# CONNECTOR.net
KiCad netlist of a schematic drawn in Altium Designer
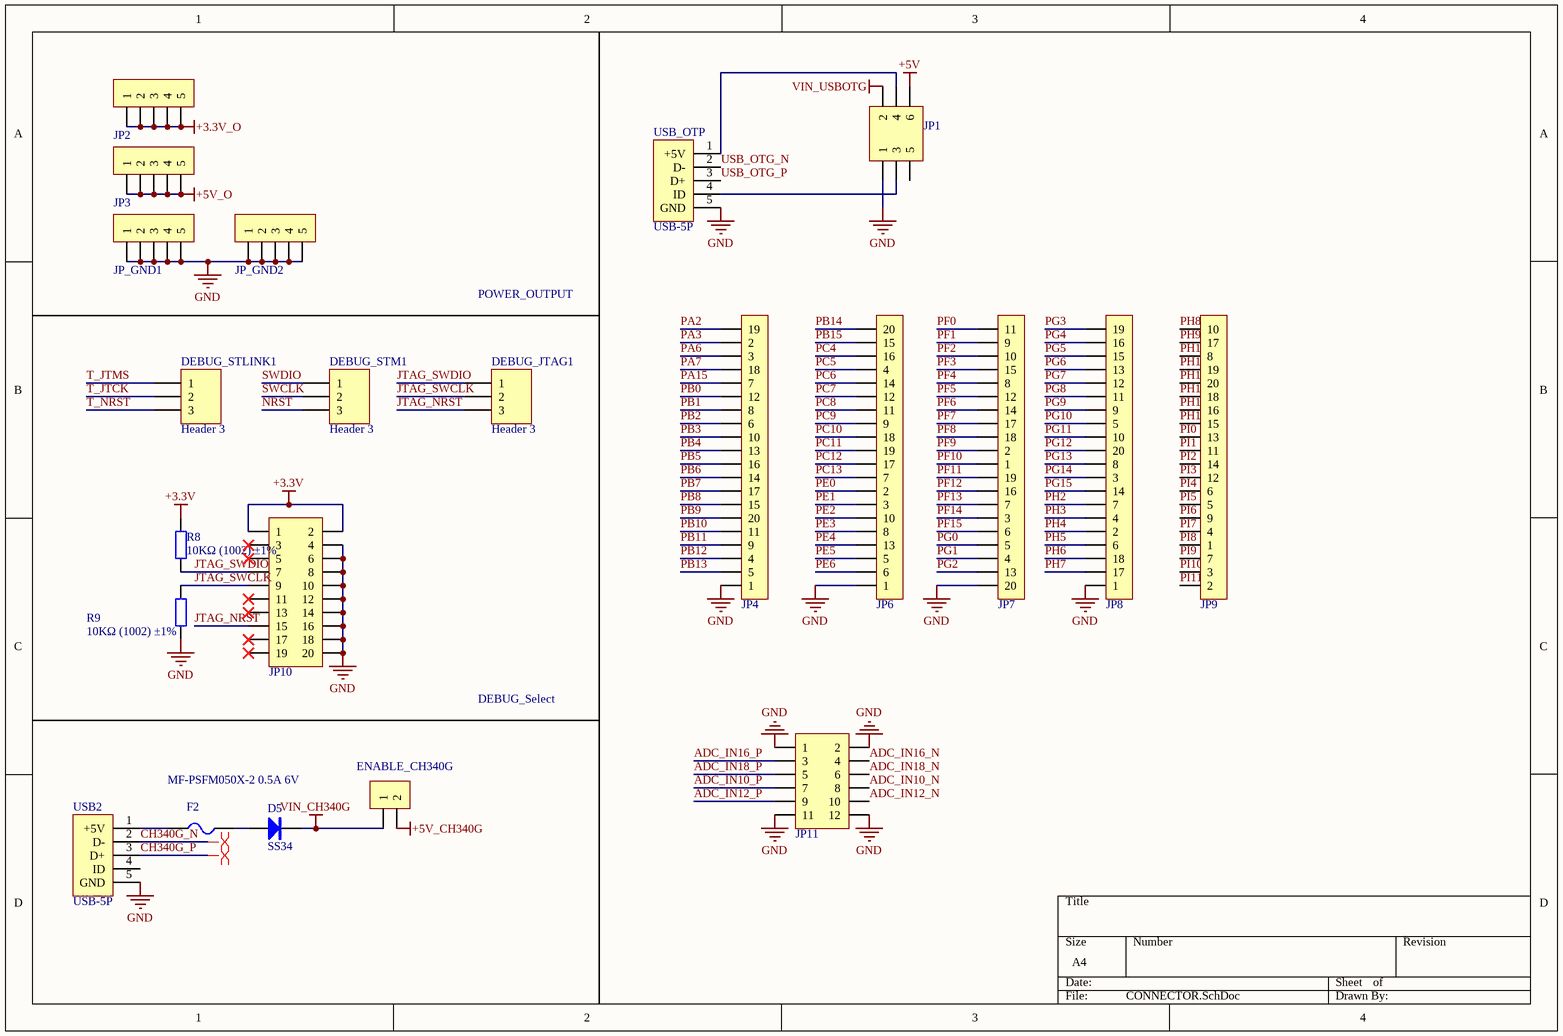
[diagram p0: CONNECTOR.SchDoc]

(export (version "E")
  (design (tool "Eeschema 10.0.6"))
  (components
    (comp (ref "D5")
      (value "SS34")
      (footprint "SMC")
      (description "肖特基二极管")
      (fields (field (name "版权归属") "源创客"))
      (libsource (lib "8.1   - 二极管-整流桥") (part "SS34"))
    )
    (comp (ref "DEBUG_JTAG1")
      (value "Header 3")
      (footprint "HDR1X3")
      (description "Header, 3-Pin")
      (fields (field (name "PUBLISHER") "Altium Limited"))
      (libsource (lib "Miscellaneous Connectors") (part "Header 3"))
    )
    (comp (ref "DEBUG_STLINK1")
      (value "Header 3")
      (footprint "HDR1X3")
      (description "Header, 3-Pin")
      (fields (field (name "PUBLISHER") "Altium Limited"))
      (libsource (lib "Miscellaneous Connectors") (part "Header 3"))
    )
    (comp (ref "DEBUG_STM1")
      (value "Header 3")
      (footprint "HDR1X3")
      (description "Header, 3-Pin")
      (fields (field (name "PUBLISHER") "Altium Limited"))
      (libsource (lib "Miscellaneous Connectors") (part "Header 3"))
    )
    (comp (ref "ENABLE_CH340G")
      (value "HDR-1X2")
      (footprint "HDR2.54-LI-2P")
      (description "2P接插件")
      (fields (field (name "版权归属") "源创客"))
      (libsource (lib "4.5   - 接插件-脚距2.54") (part "Header 2"))
    )
    (comp (ref "F2")
      (value "MF-PSFM050X-2 0.5A 6V")
      (footprint "FU 0805")
      (description "贴片保险丝")
      (fields (field (name "版权归属") "源创客"))
      (libsource (lib "10.1 - 保险丝-晶振") (part "FU"))
    )
    (comp (ref "JP1")
      (value "Header3X2")
      (footprint "HDR2.54-LI-2x3P")
      (description "3*2P接插件")
      (fields (field (name "版权归属") "源创客"))
      (libsource (lib "4.5   - 接插件-脚距2.54") (part "Header 3X2"))
    )
    (comp (ref "JP2")
      (value "HDR-1X5")
      (footprint "HDR2.54-LI-5P")
      (description "5P接插件")
      (fields (field (name "版权归属") "源创客"))
      (libsource (lib "4.5   - 接插件-脚距2.54") (part "Header 5"))
    )
    (comp (ref "JP3")
      (value "HDR-1X5")
      (footprint "HDR2.54-LI-5P")
      (description "5P接插件")
      (fields (field (name "版权归属") "源创客"))
      (libsource (lib "4.5   - 接插件-脚距2.54") (part "Header 5"))
    )
    (comp (ref "JP4")
      (value "HDR-1X20")
      (footprint "HDR2.54-LI-20P")
      (description "20P接插件")
      (fields (field (name "版权归属") "源创客"))
      (libsource (lib "4.5   - 接插件-脚距2.54") (part "Header 20"))
    )
    (comp (ref "JP6")
      (value "HDR-1X20")
      (footprint "HDR2.54-LI-20P")
      (description "20P接插件")
      (fields (field (name "版权归属") "源创客"))
      (libsource (lib "") (part "Header 20_1"))
    )
    (comp (ref "JP7")
      (value "HDR-1X20")
      (footprint "HDR2.54-LI-20P")
      (description "20P接插件")
      (fields (field (name "版权归属") "源创客"))
      (libsource (lib "") (part "Header 20_3"))
    )
    (comp (ref "JP8")
      (value "HDR-1X20")
      (footprint "HDR2.54-LI-20P")
      (description "20P接插件")
      (fields (field (name "版权归属") "源创客"))
      (libsource (lib "") (part "Header 20_2"))
    )
    (comp (ref "JP9")
      (value "HDR-1X20")
      (footprint "HDR2.54-LI-20P")
      (description "20P接插件")
      (fields (field (name "版权归属") "源创客"))
      (libsource (lib "") (part "Header 20_4"))
    )
    (comp (ref "JP10")
      (value "Header 2X10")
      (footprint "IDC2.54-LI-2x10P")
      (description "10*2P接插件")
      (fields (field (name "版权归属") "源创客"))
      (libsource (lib "4.5   - 接插件-脚距2.54") (part "Header 10X2"))
    )
    (comp (ref "JP11")
      (value "Header 6X2")
      (footprint "HDR2.54-LI-2x6P")
      (description "6*2P接插件")
      (fields (field (name "版权归属") "源创客"))
      (libsource (lib "4.5   - 接插件-脚距2.54") (part "Header  6X2"))
    )
    (comp (ref "JP_GND1")
      (value "HDR-1X5")
      (footprint "HDR2.54-LI-5P")
      (description "5P接插件")
      (fields (field (name "版权归属") "源创客"))
      (libsource (lib "4.5   - 接插件-脚距2.54") (part "Header 5"))
    )
    (comp (ref "JP_GND2")
      (value "HDR-1X5")
      (footprint "HDR2.54-LI-5P")
      (description "5P接插件")
      (fields (field (name "版权归属") "源创客"))
      (libsource (lib "4.5   - 接插件-脚距2.54") (part "Header 5"))
    )
    (comp (ref "R8")
      (value "10KΩ (1002) ±1%")
      (footprint "0603_R")
      (description "贴片电阻")
      (libsource (lib "RES") (part "0603 10KΩ (1002) 1%"))
    )
    (comp (ref "R9")
      (value "10KΩ (1002) ±1%")
      (footprint "0603_R")
      (description "贴片电阻")
      (libsource (lib "RES") (part "0603 10KΩ (1002) 1%"))
    )
    (comp (ref "USB2")
      (value "USB-5P")
      (footprint "USB-MICRO_D")
      (description "微型USB母座")
      (fields (field (name "版权归属") "源创客"))
      (libsource (lib "4.1   - 接口类") (part "USB-5P"))
    )
    (comp (ref "USB_OTP")
      (value "USB-5P")
      (footprint "USB-MICRO_D")
      (description "微型USB母座")
      (fields (field (name "版权归属") "源创客"))
      (libsource (lib "4.1   - 接口类") (part "USB-5P"))
    )
  )
  (nets
    (net (code "1") (name "+3.3V") (class "Default")
      (node (ref "JP10") (pin "1") (pinfunction "1_1") (pintype "passive"))
      (node (ref "JP10") (pin "2") (pinfunction "2_2") (pintype "passive"))
      (node (ref "R8") (pin "2") (pinfunction "2_2") (pintype "passive"))
    )
    (net (code "2") (name "+3.3V_O") (class "Default")
      (node (ref "JP2") (pin "1") (pinfunction "1_1") (pintype "passive"))
      (node (ref "JP2") (pin "2") (pinfunction "2_2") (pintype "passive"))
      (node (ref "JP2") (pin "3") (pinfunction "3_3") (pintype "passive"))
      (node (ref "JP2") (pin "4") (pinfunction "4_4") (pintype "passive"))
      (node (ref "JP2") (pin "5") (pinfunction "5_5") (pintype "passive"))
    )
    (net (code "3") (name "+5V") (class "Default")
      (node (ref "JP1") (pin "6") (pinfunction "6_6") (pintype "passive"))
    )
    (net (code "4") (name "+5V_CH340G") (class "Default")
      (node (ref "ENABLE_CH340G") (pin "2") (pinfunction "2_2") (pintype "passive"))
    )
    (net (code "5") (name "+5V_O") (class "Default")
      (node (ref "JP3") (pin "1") (pinfunction "1_1") (pintype "passive"))
      (node (ref "JP3") (pin "2") (pinfunction "2_2") (pintype "passive"))
      (node (ref "JP3") (pin "3") (pinfunction "3_3") (pintype "passive"))
      (node (ref "JP3") (pin "4") (pinfunction "4_4") (pintype "passive"))
      (node (ref "JP3") (pin "5") (pinfunction "5_5") (pintype "passive"))
    )
    (net (code "6") (name "/ADC_IN10_N") (class "Default")
      (node (ref "JP11") (pin "8") (pinfunction "8_8") (pintype "passive"))
    )
    (net (code "7") (name "/ADC_IN10_P") (class "Default")
      (node (ref "JP11") (pin "7") (pinfunction "7_7") (pintype "passive"))
    )
    (net (code "8") (name "/ADC_IN12_N") (class "Default")
      (node (ref "JP11") (pin "10") (pinfunction "10_10") (pintype "passive"))
    )
    (net (code "9") (name "/ADC_IN12_P") (class "Default")
      (node (ref "JP11") (pin "9") (pinfunction "9_9") (pintype "passive"))
    )
    (net (code "10") (name "/ADC_IN16_N") (class "Default")
      (node (ref "JP11") (pin "4") (pinfunction "4_4") (pintype "passive"))
    )
    (net (code "11") (name "/ADC_IN16_P") (class "Default")
      (node (ref "JP11") (pin "3") (pinfunction "3_3") (pintype "passive"))
    )
    (net (code "12") (name "/ADC_IN18_N") (class "Default")
      (node (ref "JP11") (pin "6") (pinfunction "6_6") (pintype "passive"))
    )
    (net (code "13") (name "/ADC_IN18_P") (class "Default")
      (node (ref "JP11") (pin "5") (pinfunction "5_5") (pintype "passive"))
    )
    (net (code "14") (name "/CH340G_N") (class "Default")
      (node (ref "USB2") (pin "2") (pinfunction "D-_2") (pintype "passive"))
    )
    (net (code "15") (name "/CH340G_P") (class "Default")
      (node (ref "USB2") (pin "3") (pinfunction "D+_3") (pintype "passive"))
    )
    (net (code "16") (name "/JTAG_NRST") (class "Default")
      (node (ref "DEBUG_JTAG1") (pin "3") (pinfunction "3_3") (pintype "passive"))
      (node (ref "JP10") (pin "15") (pinfunction "15_15") (pintype "passive"))
    )
    (net (code "17") (name "/JTAG_SWCLK") (class "Default")
      (node (ref "DEBUG_JTAG1") (pin "2") (pinfunction "2_2") (pintype "passive"))
      (node (ref "JP10") (pin "9") (pinfunction "9_9") (pintype "passive"))
      (node (ref "R9") (pin "2") (pinfunction "2_2") (pintype "passive"))
    )
    (net (code "18") (name "/JTAG_SWDIO") (class "Default")
      (node (ref "DEBUG_JTAG1") (pin "1") (pinfunction "1_1") (pintype "passive"))
      (node (ref "JP10") (pin "7") (pinfunction "7_7") (pintype "passive"))
      (node (ref "R8") (pin "1") (pinfunction "1_1") (pintype "passive"))
    )
    (net (code "19") (name "/NRST") (class "Default")
      (node (ref "DEBUG_STM1") (pin "3") (pinfunction "3_3") (pintype "passive"))
    )
    (net (code "20") (name "/PA2") (class "Default")
      (node (ref "JP4") (pin "19") (pinfunction "19_19") (pintype "passive"))
    )
    (net (code "21") (name "/PA3") (class "Default")
      (node (ref "JP4") (pin "2") (pinfunction "2_2") (pintype "passive"))
    )
    (net (code "22") (name "/PA6") (class "Default")
      (node (ref "JP4") (pin "3") (pinfunction "3_3") (pintype "passive"))
    )
    (net (code "23") (name "/PA7") (class "Default")
      (node (ref "JP4") (pin "18") (pinfunction "18_18") (pintype "passive"))
    )
    (net (code "24") (name "/PA15") (class "Default")
      (node (ref "JP4") (pin "7") (pinfunction "7_7") (pintype "passive"))
    )
    (net (code "25") (name "/PB0") (class "Default")
      (node (ref "JP4") (pin "12") (pinfunction "12_12") (pintype "passive"))
    )
    (net (code "26") (name "/PB1") (class "Default")
      (node (ref "JP4") (pin "8") (pinfunction "8_8") (pintype "passive"))
    )
    (net (code "27") (name "/PB2") (class "Default")
      (node (ref "JP4") (pin "6") (pinfunction "6_6") (pintype "passive"))
    )
    (net (code "28") (name "/PB3") (class "Default")
      (node (ref "JP4") (pin "10") (pinfunction "10_10") (pintype "passive"))
    )
    (net (code "29") (name "/PB4") (class "Default")
      (node (ref "JP4") (pin "13") (pinfunction "13_13") (pintype "passive"))
    )
    (net (code "30") (name "/PB5") (class "Default")
      (node (ref "JP4") (pin "16") (pinfunction "16_16") (pintype "passive"))
    )
    (net (code "31") (name "/PB6") (class "Default")
      (node (ref "JP4") (pin "14") (pinfunction "14_14") (pintype "passive"))
    )
    (net (code "32") (name "/PB7") (class "Default")
      (node (ref "JP4") (pin "17") (pinfunction "17_17") (pintype "passive"))
    )
    (net (code "33") (name "/PB8") (class "Default")
      (node (ref "JP4") (pin "15") (pinfunction "15_15") (pintype "passive"))
    )
    (net (code "34") (name "/PB9") (class "Default")
      (node (ref "JP4") (pin "20") (pinfunction "20_20") (pintype "passive"))
    )
    (net (code "35") (name "/PB10") (class "Default")
      (node (ref "JP4") (pin "11") (pinfunction "11_11") (pintype "passive"))
    )
    (net (code "36") (name "/PB11") (class "Default")
      (node (ref "JP4") (pin "9") (pinfunction "9_9") (pintype "passive"))
    )
    (net (code "37") (name "/PB12") (class "Default")
      (node (ref "JP4") (pin "4") (pinfunction "4_4") (pintype "passive"))
    )
    (net (code "38") (name "/PB13") (class "Default")
      (node (ref "JP4") (pin "5") (pinfunction "5_5") (pintype "passive"))
    )
    (net (code "39") (name "/PB14") (class "Default")
      (node (ref "JP6") (pin "20") (pinfunction "20_20") (pintype "passive"))
    )
    (net (code "40") (name "/PB15") (class "Default")
      (node (ref "JP6") (pin "15") (pinfunction "15_15") (pintype "passive"))
    )
    (net (code "41") (name "/PC4") (class "Default")
      (node (ref "JP6") (pin "16") (pinfunction "16_16") (pintype "passive"))
    )
    (net (code "42") (name "/PC5") (class "Default")
      (node (ref "JP6") (pin "4") (pinfunction "4_4") (pintype "passive"))
    )
    (net (code "43") (name "/PC6") (class "Default")
      (node (ref "JP6") (pin "14") (pinfunction "14_14") (pintype "passive"))
    )
    (net (code "44") (name "/PC7") (class "Default")
      (node (ref "JP6") (pin "12") (pinfunction "12_12") (pintype "passive"))
    )
    (net (code "45") (name "/PC8") (class "Default")
      (node (ref "JP6") (pin "11") (pinfunction "11_11") (pintype "passive"))
    )
    (net (code "46") (name "/PC9") (class "Default")
      (node (ref "JP6") (pin "9") (pinfunction "9_9") (pintype "passive"))
    )
    (net (code "47") (name "/PC10") (class "Default")
      (node (ref "JP6") (pin "18") (pinfunction "18_18") (pintype "passive"))
    )
    (net (code "48") (name "/PC11") (class "Default")
      (node (ref "JP6") (pin "19") (pinfunction "19_19") (pintype "passive"))
    )
    (net (code "49") (name "/PC12") (class "Default")
      (node (ref "JP6") (pin "17") (pinfunction "17_17") (pintype "passive"))
    )
    (net (code "50") (name "/PC13") (class "Default")
      (node (ref "JP6") (pin "7") (pinfunction "7_7") (pintype "passive"))
    )
    (net (code "51") (name "/PE0") (class "Default")
      (node (ref "JP6") (pin "2") (pinfunction "2_2") (pintype "passive"))
    )
    (net (code "52") (name "/PE1") (class "Default")
      (node (ref "JP6") (pin "3") (pinfunction "3_3") (pintype "passive"))
    )
    (net (code "53") (name "/PE2") (class "Default")
      (node (ref "JP6") (pin "10") (pinfunction "10_10") (pintype "passive"))
    )
    (net (code "54") (name "/PE3") (class "Default")
      (node (ref "JP6") (pin "8") (pinfunction "8_8") (pintype "passive"))
    )
    (net (code "55") (name "/PE4") (class "Default")
      (node (ref "JP6") (pin "13") (pinfunction "13_13") (pintype "passive"))
    )
    (net (code "56") (name "/PE5") (class "Default")
      (node (ref "JP6") (pin "5") (pinfunction "5_5") (pintype "passive"))
    )
    (net (code "57") (name "/PE6") (class "Default")
      (node (ref "JP6") (pin "6") (pinfunction "6_6") (pintype "passive"))
    )
    (net (code "58") (name "/PF0") (class "Default")
      (node (ref "JP7") (pin "11") (pinfunction "11_11") (pintype "passive"))
    )
    (net (code "59") (name "/PF1") (class "Default")
      (node (ref "JP7") (pin "9") (pinfunction "9_9") (pintype "passive"))
    )
    (net (code "60") (name "/PF2") (class "Default")
      (node (ref "JP7") (pin "10") (pinfunction "10_10") (pintype "passive"))
    )
    (net (code "61") (name "/PF3") (class "Default")
      (node (ref "JP7") (pin "15") (pinfunction "15_15") (pintype "passive"))
    )
    (net (code "62") (name "/PF4") (class "Default")
      (node (ref "JP7") (pin "8") (pinfunction "8_8") (pintype "passive"))
    )
    (net (code "63") (name "/PF5") (class "Default")
      (node (ref "JP7") (pin "12") (pinfunction "12_12") (pintype "passive"))
    )
    (net (code "64") (name "/PF6") (class "Default")
      (node (ref "JP7") (pin "14") (pinfunction "14_14") (pintype "passive"))
    )
    (net (code "65") (name "/PF7") (class "Default")
      (node (ref "JP7") (pin "17") (pinfunction "17_17") (pintype "passive"))
    )
    (net (code "66") (name "/PF8") (class "Default")
      (node (ref "JP7") (pin "18") (pinfunction "18_18") (pintype "passive"))
    )
    (net (code "67") (name "/PF9") (class "Default")
      (node (ref "JP7") (pin "2") (pinfunction "2_2") (pintype "passive"))
    )
    (net (code "68") (name "/PF10") (class "Default")
      (node (ref "JP7") (pin "1") (pinfunction "1_1") (pintype "passive"))
    )
    (net (code "69") (name "/PF11") (class "Default")
      (node (ref "JP7") (pin "19") (pinfunction "19_19") (pintype "passive"))
    )
    (net (code "70") (name "/PF12") (class "Default")
      (node (ref "JP7") (pin "16") (pinfunction "16_16") (pintype "passive"))
    )
    (net (code "71") (name "/PF13") (class "Default")
      (node (ref "JP7") (pin "7") (pinfunction "7_7") (pintype "passive"))
    )
    (net (code "72") (name "/PF14") (class "Default")
      (node (ref "JP7") (pin "3") (pinfunction "3_3") (pintype "passive"))
    )
    (net (code "73") (name "/PF15") (class "Default")
      (node (ref "JP7") (pin "6") (pinfunction "6_6") (pintype "passive"))
    )
    (net (code "74") (name "/PG0") (class "Default")
      (node (ref "JP7") (pin "5") (pinfunction "5_5") (pintype "passive"))
    )
    (net (code "75") (name "/PG1") (class "Default")
      (node (ref "JP7") (pin "4") (pinfunction "4_4") (pintype "passive"))
    )
    (net (code "76") (name "/PG2") (class "Default")
      (node (ref "JP7") (pin "13") (pinfunction "13_13") (pintype "passive"))
    )
    (net (code "77") (name "/PG3") (class "Default")
      (node (ref "JP8") (pin "19") (pinfunction "19_19") (pintype "passive"))
    )
    (net (code "78") (name "/PG4") (class "Default")
      (node (ref "JP8") (pin "16") (pinfunction "16_16") (pintype "passive"))
    )
    (net (code "79") (name "/PG5") (class "Default")
      (node (ref "JP8") (pin "15") (pinfunction "15_15") (pintype "passive"))
    )
    (net (code "80") (name "/PG6") (class "Default")
      (node (ref "JP8") (pin "13") (pinfunction "13_13") (pintype "passive"))
    )
    (net (code "81") (name "/PG7") (class "Default")
      (node (ref "JP8") (pin "12") (pinfunction "12_12") (pintype "passive"))
    )
    (net (code "82") (name "/PG8") (class "Default")
      (node (ref "JP8") (pin "11") (pinfunction "11_11") (pintype "passive"))
    )
    (net (code "83") (name "/PG9") (class "Default")
      (node (ref "JP8") (pin "9") (pinfunction "9_9") (pintype "passive"))
    )
    (net (code "84") (name "/PG10") (class "Default")
      (node (ref "JP8") (pin "5") (pinfunction "5_5") (pintype "passive"))
    )
    (net (code "85") (name "/PG11") (class "Default")
      (node (ref "JP8") (pin "10") (pinfunction "10_10") (pintype "passive"))
    )
    (net (code "86") (name "/PG12") (class "Default")
      (node (ref "JP8") (pin "20") (pinfunction "20_20") (pintype "passive"))
    )
    (net (code "87") (name "/PG13") (class "Default")
      (node (ref "JP8") (pin "8") (pinfunction "8_8") (pintype "passive"))
    )
    (net (code "88") (name "/PG14") (class "Default")
      (node (ref "JP8") (pin "3") (pinfunction "3_3") (pintype "passive"))
    )
    (net (code "89") (name "/PG15") (class "Default")
      (node (ref "JP8") (pin "14") (pinfunction "14_14") (pintype "passive"))
    )
    (net (code "90") (name "/PH2") (class "Default")
      (node (ref "JP8") (pin "7") (pinfunction "7_7") (pintype "passive"))
    )
    (net (code "91") (name "/PH3") (class "Default")
      (node (ref "JP8") (pin "4") (pinfunction "4_4") (pintype "passive"))
    )
    (net (code "92") (name "/PH4") (class "Default")
      (node (ref "JP8") (pin "2") (pinfunction "2_2") (pintype "passive"))
    )
    (net (code "93") (name "/PH5") (class "Default")
      (node (ref "JP8") (pin "6") (pinfunction "6_6") (pintype "passive"))
    )
    (net (code "94") (name "/PH6") (class "Default")
      (node (ref "JP8") (pin "18") (pinfunction "18_18") (pintype "passive"))
    )
    (net (code "95") (name "/PH7") (class "Default")
      (node (ref "JP8") (pin "17") (pinfunction "17_17") (pintype "passive"))
    )
    (net (code "96") (name "/PH8") (class "Default")
      (node (ref "JP9") (pin "10") (pinfunction "10_10") (pintype "passive"))
    )
    (net (code "97") (name "/PH9") (class "Default")
      (node (ref "JP9") (pin "17") (pinfunction "17_17") (pintype "passive"))
    )
    (net (code "98") (name "/PH10") (class "Default")
      (node (ref "JP9") (pin "8") (pinfunction "8_8") (pintype "passive"))
    )
    (net (code "99") (name "/PH11") (class "Default")
      (node (ref "JP9") (pin "19") (pinfunction "19_19") (pintype "passive"))
    )
    (net (code "100") (name "/PH12") (class "Default")
      (node (ref "JP9") (pin "20") (pinfunction "20_20") (pintype "passive"))
    )
    (net (code "101") (name "/PH13") (class "Default")
      (node (ref "JP9") (pin "18") (pinfunction "18_18") (pintype "passive"))
    )
    (net (code "102") (name "/PH14") (class "Default")
      (node (ref "JP9") (pin "16") (pinfunction "16_16") (pintype "passive"))
    )
    (net (code "103") (name "/PH15") (class "Default")
      (node (ref "JP9") (pin "15") (pinfunction "15_15") (pintype "passive"))
    )
    (net (code "104") (name "/PI0") (class "Default")
      (node (ref "JP9") (pin "13") (pinfunction "13_13") (pintype "passive"))
    )
    (net (code "105") (name "/PI1") (class "Default")
      (node (ref "JP9") (pin "11") (pinfunction "11_11") (pintype "passive"))
    )
    (net (code "106") (name "/PI2") (class "Default")
      (node (ref "JP9") (pin "14") (pinfunction "14_14") (pintype "passive"))
    )
    (net (code "107") (name "/PI3") (class "Default")
      (node (ref "JP9") (pin "12") (pinfunction "12_12") (pintype "passive"))
    )
    (net (code "108") (name "/PI4") (class "Default")
      (node (ref "JP9") (pin "6") (pinfunction "6_6") (pintype "passive"))
    )
    (net (code "109") (name "/PI5") (class "Default")
      (node (ref "JP9") (pin "5") (pinfunction "5_5") (pintype "passive"))
    )
    (net (code "110") (name "/PI6") (class "Default")
      (node (ref "JP9") (pin "9") (pinfunction "9_9") (pintype "passive"))
    )
    (net (code "111") (name "/PI7") (class "Default")
      (node (ref "JP9") (pin "4") (pinfunction "4_4") (pintype "passive"))
    )
    (net (code "112") (name "/PI8") (class "Default")
      (node (ref "JP9") (pin "1") (pinfunction "1_1") (pintype "passive"))
    )
    (net (code "113") (name "/PI9") (class "Default")
      (node (ref "JP9") (pin "7") (pinfunction "7_7") (pintype "passive"))
    )
    (net (code "114") (name "/PI10") (class "Default")
      (node (ref "JP9") (pin "3") (pinfunction "3_3") (pintype "passive"))
    )
    (net (code "115") (name "/PI11") (class "Default")
      (node (ref "JP9") (pin "2") (pinfunction "2_2") (pintype "passive"))
    )
    (net (code "116") (name "/SWCLK") (class "Default")
      (node (ref "DEBUG_STM1") (pin "2") (pinfunction "2_2") (pintype "passive"))
    )
    (net (code "117") (name "/SWDIO") (class "Default")
      (node (ref "DEBUG_STM1") (pin "1") (pinfunction "1_1") (pintype "passive"))
    )
    (net (code "118") (name "/T_JTCK") (class "Default")
      (node (ref "DEBUG_STLINK1") (pin "2") (pinfunction "2_2") (pintype "passive"))
    )
    (net (code "119") (name "/T_JTMS") (class "Default")
      (node (ref "DEBUG_STLINK1") (pin "1") (pinfunction "1_1") (pintype "passive"))
    )
    (net (code "120") (name "/T_NRST") (class "Default")
      (node (ref "DEBUG_STLINK1") (pin "3") (pinfunction "3_3") (pintype "passive"))
    )
    (net (code "121") (name "/USB_OTG_N") (class "Default")
      (node (ref "USB_OTP") (pin "2") (pinfunction "D-_2") (pintype "passive"))
    )
    (net (code "122") (name "/USB_OTG_P") (class "Default")
      (node (ref "USB_OTP") (pin "3") (pinfunction "D+_3") (pintype "passive"))
    )
    (net (code "123") (name "GND") (class "Default")
      (node (ref "JP1") (pin "1") (pinfunction "1_1") (pintype "passive"))
      (node (ref "JP10") (pin "10") (pinfunction "10_10") (pintype "passive"))
      (node (ref "JP10") (pin "12") (pinfunction "12_12") (pintype "passive"))
      (node (ref "JP10") (pin "14") (pinfunction "14_14") (pintype "passive"))
      (node (ref "JP10") (pin "16") (pinfunction "16_16") (pintype "passive"))
      (node (ref "JP10") (pin "18") (pinfunction "18_18") (pintype "passive"))
      (node (ref "JP10") (pin "20") (pinfunction "20_20") (pintype "passive"))
      (node (ref "JP10") (pin "4") (pinfunction "4_4") (pintype "passive"))
      (node (ref "JP10") (pin "6") (pinfunction "6_6") (pintype "passive"))
      (node (ref "JP10") (pin "8") (pinfunction "8_8") (pintype "passive"))
      (node (ref "JP11") (pin "1") (pinfunction "1_1") (pintype "passive"))
      (node (ref "JP11") (pin "11") (pinfunction "11_11") (pintype "passive"))
      (node (ref "JP11") (pin "12") (pinfunction "12_12") (pintype "passive"))
      (node (ref "JP11") (pin "2") (pinfunction "2_2") (pintype "passive"))
      (node (ref "JP4") (pin "1") (pinfunction "1_1") (pintype "passive"))
      (node (ref "JP6") (pin "1") (pinfunction "1_1") (pintype "passive"))
      (node (ref "JP7") (pin "20") (pinfunction "20_20") (pintype "passive"))
      (node (ref "JP8") (pin "1") (pinfunction "1_1") (pintype "passive"))
      (node (ref "JP_GND1") (pin "1") (pinfunction "1_1") (pintype "passive"))
      (node (ref "JP_GND1") (pin "2") (pinfunction "2_2") (pintype "passive"))
      (node (ref "JP_GND1") (pin "3") (pinfunction "3_3") (pintype "passive"))
      (node (ref "JP_GND1") (pin "4") (pinfunction "4_4") (pintype "passive"))
      (node (ref "JP_GND1") (pin "5") (pinfunction "5_5") (pintype "passive"))
      (node (ref "JP_GND2") (pin "1") (pinfunction "1_1") (pintype "passive"))
      (node (ref "JP_GND2") (pin "2") (pinfunction "2_2") (pintype "passive"))
      (node (ref "JP_GND2") (pin "3") (pinfunction "3_3") (pintype "passive"))
      (node (ref "JP_GND2") (pin "4") (pinfunction "4_4") (pintype "passive"))
      (node (ref "JP_GND2") (pin "5") (pinfunction "5_5") (pintype "passive"))
      (node (ref "R9") (pin "1") (pinfunction "1_1") (pintype "passive"))
      (node (ref "USB2") (pin "5") (pinfunction "GND_5") (pintype "passive"))
      (node (ref "USB_OTP") (pin "5") (pinfunction "GND_5") (pintype "passive"))
    )
    (net (code "124") (name "Net-(D5-A)") (class "Default")
      (node (ref "D5") (pin "1") (pinfunction "A_1") (pintype "passive"))
      (node (ref "F2") (pin "2") (pinfunction "2_2") (pintype "passive"))
    )
    (net (code "125") (name "Net-(USB2-+5V)") (class "Default")
      (node (ref "F2") (pin "1") (pinfunction "1_1") (pintype "passive"))
      (node (ref "USB2") (pin "1") (pinfunction "+5V_1") (pintype "passive"))
    )
    (net (code "126") (name "Net-(USB_OTP-+5V)") (class "Default")
      (node (ref "JP1") (pin "4") (pinfunction "4_4") (pintype "passive"))
      (node (ref "USB_OTP") (pin "1") (pinfunction "+5V_1") (pintype "passive"))
    )
    (net (code "127") (name "Net-(USB_OTP-ID)") (class "Default")
      (node (ref "JP1") (pin "3") (pinfunction "3_3") (pintype "passive"))
      (node (ref "USB_OTP") (pin "4") (pinfunction "ID_4") (pintype "passive"))
    )
    (net (code "128") (name "VIN_CH340G") (class "Default")
      (node (ref "D5") (pin "2") (pinfunction "K_2") (pintype "passive"))
      (node (ref "ENABLE_CH340G") (pin "1") (pinfunction "1_1") (pintype "passive"))
    )
    (net (code "129") (name "VIN_USBOTG") (class "Default")
      (node (ref "JP1") (pin "2") (pinfunction "2_2") (pintype "passive"))
    )
    (net (code "130") (name "unconnected-(JP1-Pad5)") (class "Default")
      (node (ref "JP1") (pin "5") (pinfunction "5_5") (pintype "passive"))
    )
    (net (code "131") (name "unconnected-(JP10-Pad3)") (class "Default")
      (node (ref "JP10") (pin "3") (pinfunction "3_3") (pintype "passive+no_connect"))
    )
    (net (code "132") (name "unconnected-(JP10-Pad5)") (class "Default")
      (node (ref "JP10") (pin "5") (pinfunction "5_5") (pintype "passive+no_connect"))
    )
    (net (code "133") (name "unconnected-(JP10-Pad11)") (class "Default")
      (node (ref "JP10") (pin "11") (pinfunction "11_11") (pintype "passive+no_connect"))
    )
    (net (code "134") (name "unconnected-(JP10-Pad13)") (class "Default")
      (node (ref "JP10") (pin "13") (pinfunction "13_13") (pintype "passive+no_connect"))
    )
    (net (code "135") (name "unconnected-(JP10-Pad17)") (class "Default")
      (node (ref "JP10") (pin "17") (pinfunction "17_17") (pintype "passive+no_connect"))
    )
    (net (code "136") (name "unconnected-(JP10-Pad19)") (class "Default")
      (node (ref "JP10") (pin "19") (pinfunction "19_19") (pintype "passive+no_connect"))
    )
    (net (code "137") (name "unconnected-(USB2-ID-Pad4)") (class "Default")
      (node (ref "USB2") (pin "4") (pinfunction "ID_4") (pintype "passive"))
    )
  )
)
